# PINS.net
KiCad netlist of a schematic drawn in Altium Designer
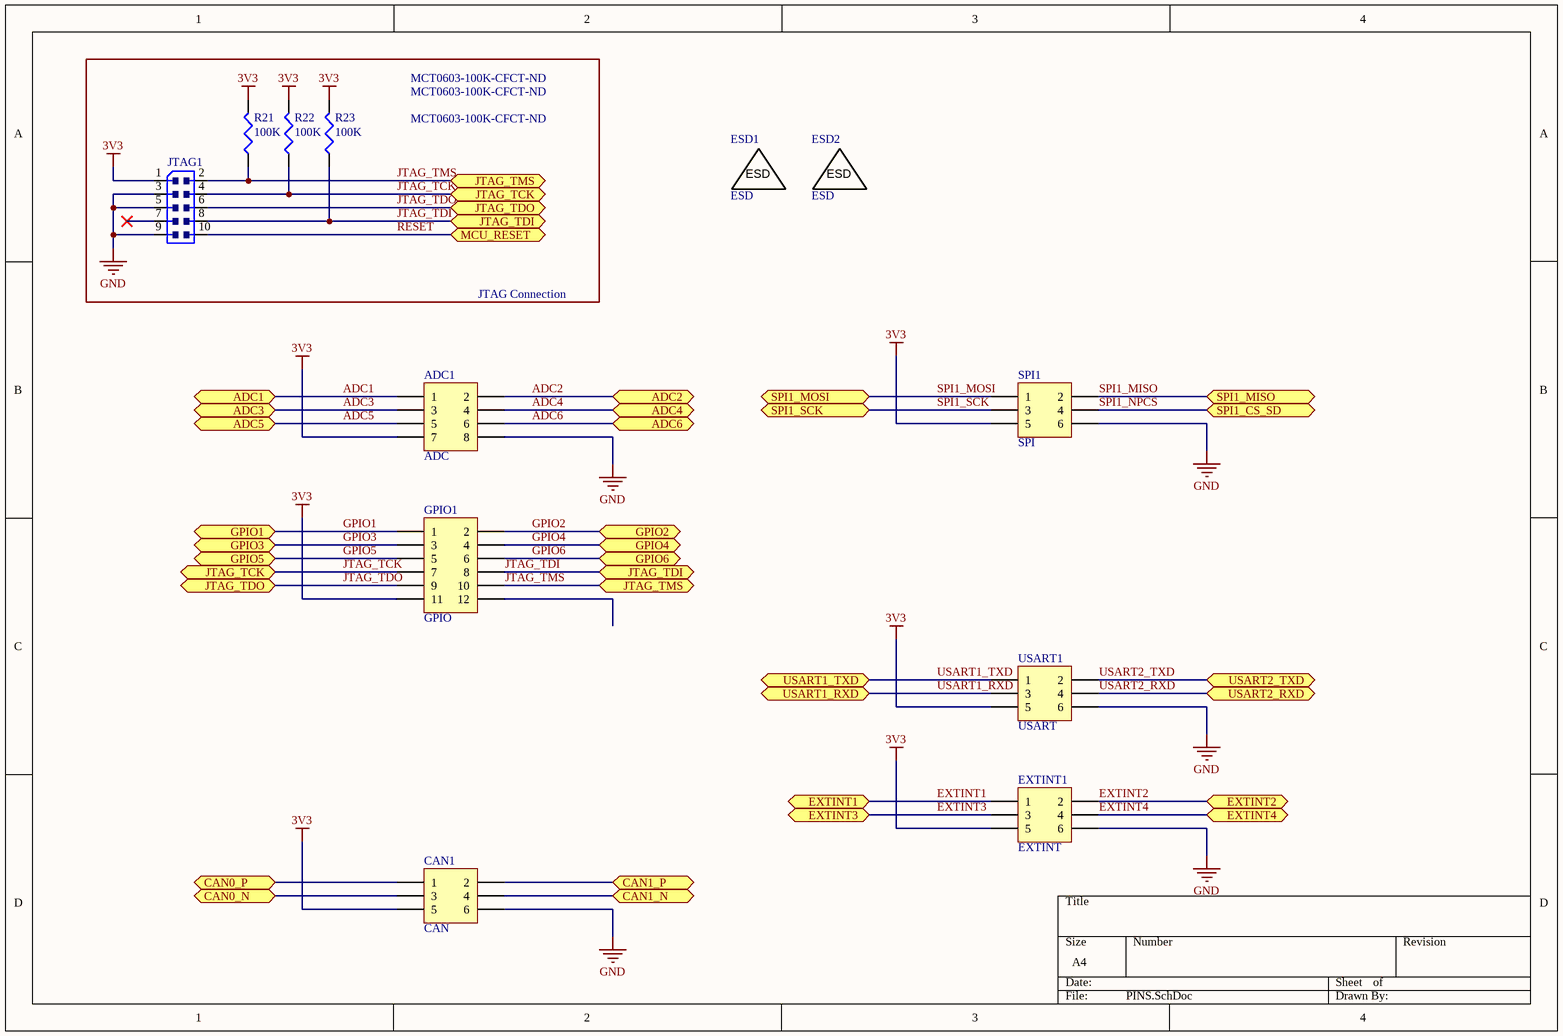
[diagram p0: PINS.SchDoc]

(export (version "E")
  (design (tool "Eeschema 10.0.6"))
  (components
    (comp (ref "ADC1")
      (value "ADC")
      (footprint "HDR2X4")
      (description "Header, 4-Pin, Dual row")
      (fields (field (name "PUBLISHER") "Altium Limited"))
      (libsource (lib "Miscellaneous Connectors") (part "Header 4X2"))
    )
    (comp (ref "CAN1")
      (value "CAN")
      (footprint "HDR2X3")
      (description "Header, 3-Pin, Dual row")
      (fields (field (name "PUBLISHER") "Altium Limited"))
      (libsource (lib "Miscellaneous Connectors") (part "Header 3X2"))
    )
    (comp (ref "ESD1")
      (value "ESD")
      (footprint "ESDSILK")
      (description "ESD LOGO")
      (libsource (lib "vh_altium_library") (part "ESD"))
    )
    (comp (ref "ESD2")
      (value "ESD")
      (footprint "ESDSILK")
      (description "ESD LOGO")
      (libsource (lib "vh_altium_library") (part "ESD"))
    )
    (comp (ref "EXTINT1")
      (value "EXTINT")
      (footprint "HDR2X3")
      (description "Header, 3-Pin, Dual row")
      (fields (field (name "PUBLISHER") "Altium Limited"))
      (libsource (lib "Miscellaneous Connectors") (part "Header 3X2"))
    )
    (comp (ref "GPIO1")
      (value "GPIO")
      (footprint "HDR2X6")
      (description "Header, 6-Pin, Dual row")
      (fields (field (name "PUBLISHER") "Altium Limited"))
      (libsource (lib "Miscellaneous Connectors") (part "Header 6X2"))
    )
    (comp (ref "JTAG1")
      (value "*")
      (footprint "PINHEAD_2X05_127")
      (libsource (lib "Arduino_Wifi_shield_v018_tG") (part "PINHEAD_PINHD-2X5PASSO127"))
    )
    (comp (ref "R21")
      (value "100K")
      (footprint "0603R-GENERIC")
      (description "Resistor")
      (fields
        (field (name "SUPPLIER PART NUMBER 1") "MCT0603-100K-CFCT-ND")
        (field (name "MANUFACTURER") "Vishay Beyschlag")
        (field (name "MANUFACTURER PART NUMBER") "MCT06030C1003FP500")
        (field (name "PUBLISHER") "Altium Limited")
      )
      (libsource (lib "Miscellaneous Devices") (part "Res3"))
    )
    (comp (ref "R22")
      (value "100K")
      (footprint "0603R-GENERIC")
      (description "Resistor")
      (fields
        (field (name "SUPPLIER PART NUMBER 1") "MCT0603-100K-CFCT-ND")
        (field (name "MANUFACTURER") "Vishay Beyschlag")
        (field (name "MANUFACTURER PART NUMBER") "MCT06030C1003FP500")
        (field (name "PUBLISHER") "Altium Limited")
      )
      (libsource (lib "Miscellaneous Devices") (part "Res3"))
    )
    (comp (ref "R23")
      (value "100K")
      (footprint "0603R-GENERIC")
      (description "Resistor")
      (fields
        (field (name "SUPPLIER PART NUMBER 1") "MCT0603-100K-CFCT-ND")
        (field (name "MANUFACTURER") "Vishay Beyschlag")
        (field (name "MANUFACTURER PART NUMBER") "MCT06030C1003FP500")
        (field (name "PUBLISHER") "Altium Limited")
      )
      (libsource (lib "Miscellaneous Devices") (part "Res3"))
    )
    (comp (ref "SPI1")
      (value "SPI")
      (footprint "HDR2X3")
      (description "Header, 3-Pin, Dual row")
      (fields (field (name "PUBLISHER") "Altium Limited"))
      (libsource (lib "Miscellaneous Connectors") (part "Header 3X2"))
    )
    (comp (ref "USART1")
      (value "USART")
      (footprint "HDR2X3")
      (description "Header, 3-Pin, Dual row")
      (fields (field (name "PUBLISHER") "Altium Limited"))
      (libsource (lib "Miscellaneous Connectors") (part "Header 3X2"))
    )
  )
  (nets
    (net (code "1") (name "/ADC1") (class "Default")
      (node (ref "ADC1") (pin "1") (pinfunction "1_1") (pintype "passive"))
    )
    (net (code "2") (name "/ADC2") (class "Default")
      (node (ref "ADC1") (pin "2") (pinfunction "2_2") (pintype "passive"))
    )
    (net (code "3") (name "/ADC3") (class "Default")
      (node (ref "ADC1") (pin "3") (pinfunction "3_3") (pintype "passive"))
    )
    (net (code "4") (name "/ADC4") (class "Default")
      (node (ref "ADC1") (pin "4") (pinfunction "4_4") (pintype "passive"))
    )
    (net (code "5") (name "/ADC5") (class "Default")
      (node (ref "ADC1") (pin "5") (pinfunction "5_5") (pintype "passive"))
    )
    (net (code "6") (name "/ADC6") (class "Default")
      (node (ref "ADC1") (pin "6") (pinfunction "6_6") (pintype "passive"))
    )
    (net (code "7") (name "/CAN0_N") (class "Default")
      (node (ref "CAN1") (pin "3") (pinfunction "3_3") (pintype "passive"))
    )
    (net (code "8") (name "/CAN0_P") (class "Default")
      (node (ref "CAN1") (pin "1") (pinfunction "1_1") (pintype "passive"))
    )
    (net (code "9") (name "/CAN1_N") (class "Default")
      (node (ref "CAN1") (pin "4") (pinfunction "4_4") (pintype "passive"))
    )
    (net (code "10") (name "/CAN1_P") (class "Default")
      (node (ref "CAN1") (pin "2") (pinfunction "2_2") (pintype "passive"))
    )
    (net (code "11") (name "/EXTINT1") (class "Default")
      (node (ref "EXTINT1") (pin "1") (pinfunction "1_1") (pintype "passive"))
    )
    (net (code "12") (name "/EXTINT2") (class "Default")
      (node (ref "EXTINT1") (pin "2") (pinfunction "2_2") (pintype "passive"))
    )
    (net (code "13") (name "/EXTINT3") (class "Default")
      (node (ref "EXTINT1") (pin "3") (pinfunction "3_3") (pintype "passive"))
    )
    (net (code "14") (name "/EXTINT4") (class "Default")
      (node (ref "EXTINT1") (pin "4") (pinfunction "4_4") (pintype "passive"))
    )
    (net (code "15") (name "/GPIO1") (class "Default")
      (node (ref "GPIO1") (pin "1") (pinfunction "1_1") (pintype "passive"))
    )
    (net (code "16") (name "/GPIO2") (class "Default")
      (node (ref "GPIO1") (pin "2") (pinfunction "2_2") (pintype "passive"))
    )
    (net (code "17") (name "/GPIO3") (class "Default")
      (node (ref "GPIO1") (pin "3") (pinfunction "3_3") (pintype "passive"))
    )
    (net (code "18") (name "/GPIO4") (class "Default")
      (node (ref "GPIO1") (pin "4") (pinfunction "4_4") (pintype "passive"))
    )
    (net (code "19") (name "/GPIO5") (class "Default")
      (node (ref "GPIO1") (pin "5") (pinfunction "5_5") (pintype "passive"))
    )
    (net (code "20") (name "/GPIO6") (class "Default")
      (node (ref "GPIO1") (pin "6") (pinfunction "6_6") (pintype "passive"))
    )
    (net (code "21") (name "/JTAG_TCK") (class "Default")
      (node (ref "GPIO1") (pin "7") (pinfunction "7_7") (pintype "passive"))
      (node (ref "JTAG1") (pin "4") (pinfunction "4_4") (pintype "passive"))
      (node (ref "R22") (pin "1") (pinfunction "1_1") (pintype "passive"))
    )
    (net (code "22") (name "/JTAG_TDI") (class "Default")
      (node (ref "GPIO1") (pin "8") (pinfunction "8_8") (pintype "passive"))
      (node (ref "JTAG1") (pin "8") (pinfunction "8_8") (pintype "passive"))
      (node (ref "R23") (pin "1") (pinfunction "1_1") (pintype "passive"))
    )
    (net (code "23") (name "/JTAG_TDO") (class "Default")
      (node (ref "GPIO1") (pin "9") (pinfunction "9_9") (pintype "passive"))
      (node (ref "JTAG1") (pin "6") (pinfunction "6_6") (pintype "passive"))
    )
    (net (code "24") (name "/JTAG_TMS") (class "Default")
      (node (ref "GPIO1") (pin "10") (pinfunction "10_10") (pintype "passive"))
      (node (ref "JTAG1") (pin "2") (pinfunction "2_2") (pintype "passive"))
      (node (ref "R21") (pin "1") (pinfunction "1_1") (pintype "passive"))
    )
    (net (code "25") (name "/RESET") (class "Default")
      (node (ref "JTAG1") (pin "10") (pinfunction "10_10") (pintype "passive"))
    )
    (net (code "26") (name "/SPI1_MISO") (class "Default")
      (node (ref "SPI1") (pin "2") (pinfunction "2_2") (pintype "passive"))
    )
    (net (code "27") (name "/SPI1_MOSI") (class "Default")
      (node (ref "SPI1") (pin "1") (pinfunction "1_1") (pintype "passive"))
    )
    (net (code "28") (name "/SPI1_NPCS") (class "Default")
      (node (ref "SPI1") (pin "4") (pinfunction "4_4") (pintype "passive"))
    )
    (net (code "29") (name "/SPI1_SCK") (class "Default")
      (node (ref "SPI1") (pin "3") (pinfunction "3_3") (pintype "passive"))
    )
    (net (code "30") (name "/USART1_RXD") (class "Default")
      (node (ref "USART1") (pin "3") (pinfunction "3_3") (pintype "passive"))
    )
    (net (code "31") (name "/USART1_TXD") (class "Default")
      (node (ref "USART1") (pin "1") (pinfunction "1_1") (pintype "passive"))
    )
    (net (code "32") (name "/USART2_RXD") (class "Default")
      (node (ref "USART1") (pin "4") (pinfunction "4_4") (pintype "passive"))
    )
    (net (code "33") (name "/USART2_TXD") (class "Default")
      (node (ref "USART1") (pin "2") (pinfunction "2_2") (pintype "passive"))
    )
    (net (code "34") (name "3V3") (class "Default")
      (node (ref "ADC1") (pin "7") (pinfunction "7_7") (pintype "passive"))
      (node (ref "CAN1") (pin "5") (pinfunction "5_5") (pintype "passive"))
      (node (ref "EXTINT1") (pin "5") (pinfunction "5_5") (pintype "passive"))
      (node (ref "GPIO1") (pin "11") (pinfunction "11_11") (pintype "passive"))
      (node (ref "JTAG1") (pin "1") (pinfunction "1_1") (pintype "passive"))
      (node (ref "R21") (pin "2") (pinfunction "2_2") (pintype "passive"))
      (node (ref "R22") (pin "2") (pinfunction "2_2") (pintype "passive"))
      (node (ref "R23") (pin "2") (pinfunction "2_2") (pintype "passive"))
      (node (ref "SPI1") (pin "5") (pinfunction "5_5") (pintype "passive"))
      (node (ref "USART1") (pin "5") (pinfunction "5_5") (pintype "passive"))
    )
    (net (code "35") (name "GND") (class "Default")
      (node (ref "ADC1") (pin "8") (pinfunction "8_8") (pintype "passive"))
      (node (ref "CAN1") (pin "6") (pinfunction "6_6") (pintype "passive"))
      (node (ref "EXTINT1") (pin "6") (pinfunction "6_6") (pintype "passive"))
      (node (ref "JTAG1") (pin "3") (pinfunction "3_3") (pintype "passive"))
      (node (ref "JTAG1") (pin "5") (pinfunction "5_5") (pintype "passive"))
      (node (ref "JTAG1") (pin "9") (pinfunction "9_9") (pintype "passive"))
      (node (ref "SPI1") (pin "6") (pinfunction "6_6") (pintype "passive"))
      (node (ref "USART1") (pin "6") (pinfunction "6_6") (pintype "passive"))
    )
    (net (code "36") (name "unconnected-(GPIO1-Pad12)") (class "Default")
      (node (ref "GPIO1") (pin "12") (pinfunction "12_12") (pintype "passive"))
    )
    (net (code "37") (name "unconnected-(JTAG1-Pad7)") (class "Default")
      (node (ref "JTAG1") (pin "7") (pinfunction "7_7") (pintype "passive+no_connect"))
    )
  )
)
